# H3AR1.net
KiCad netlist of a schematic drawn in EAGLE
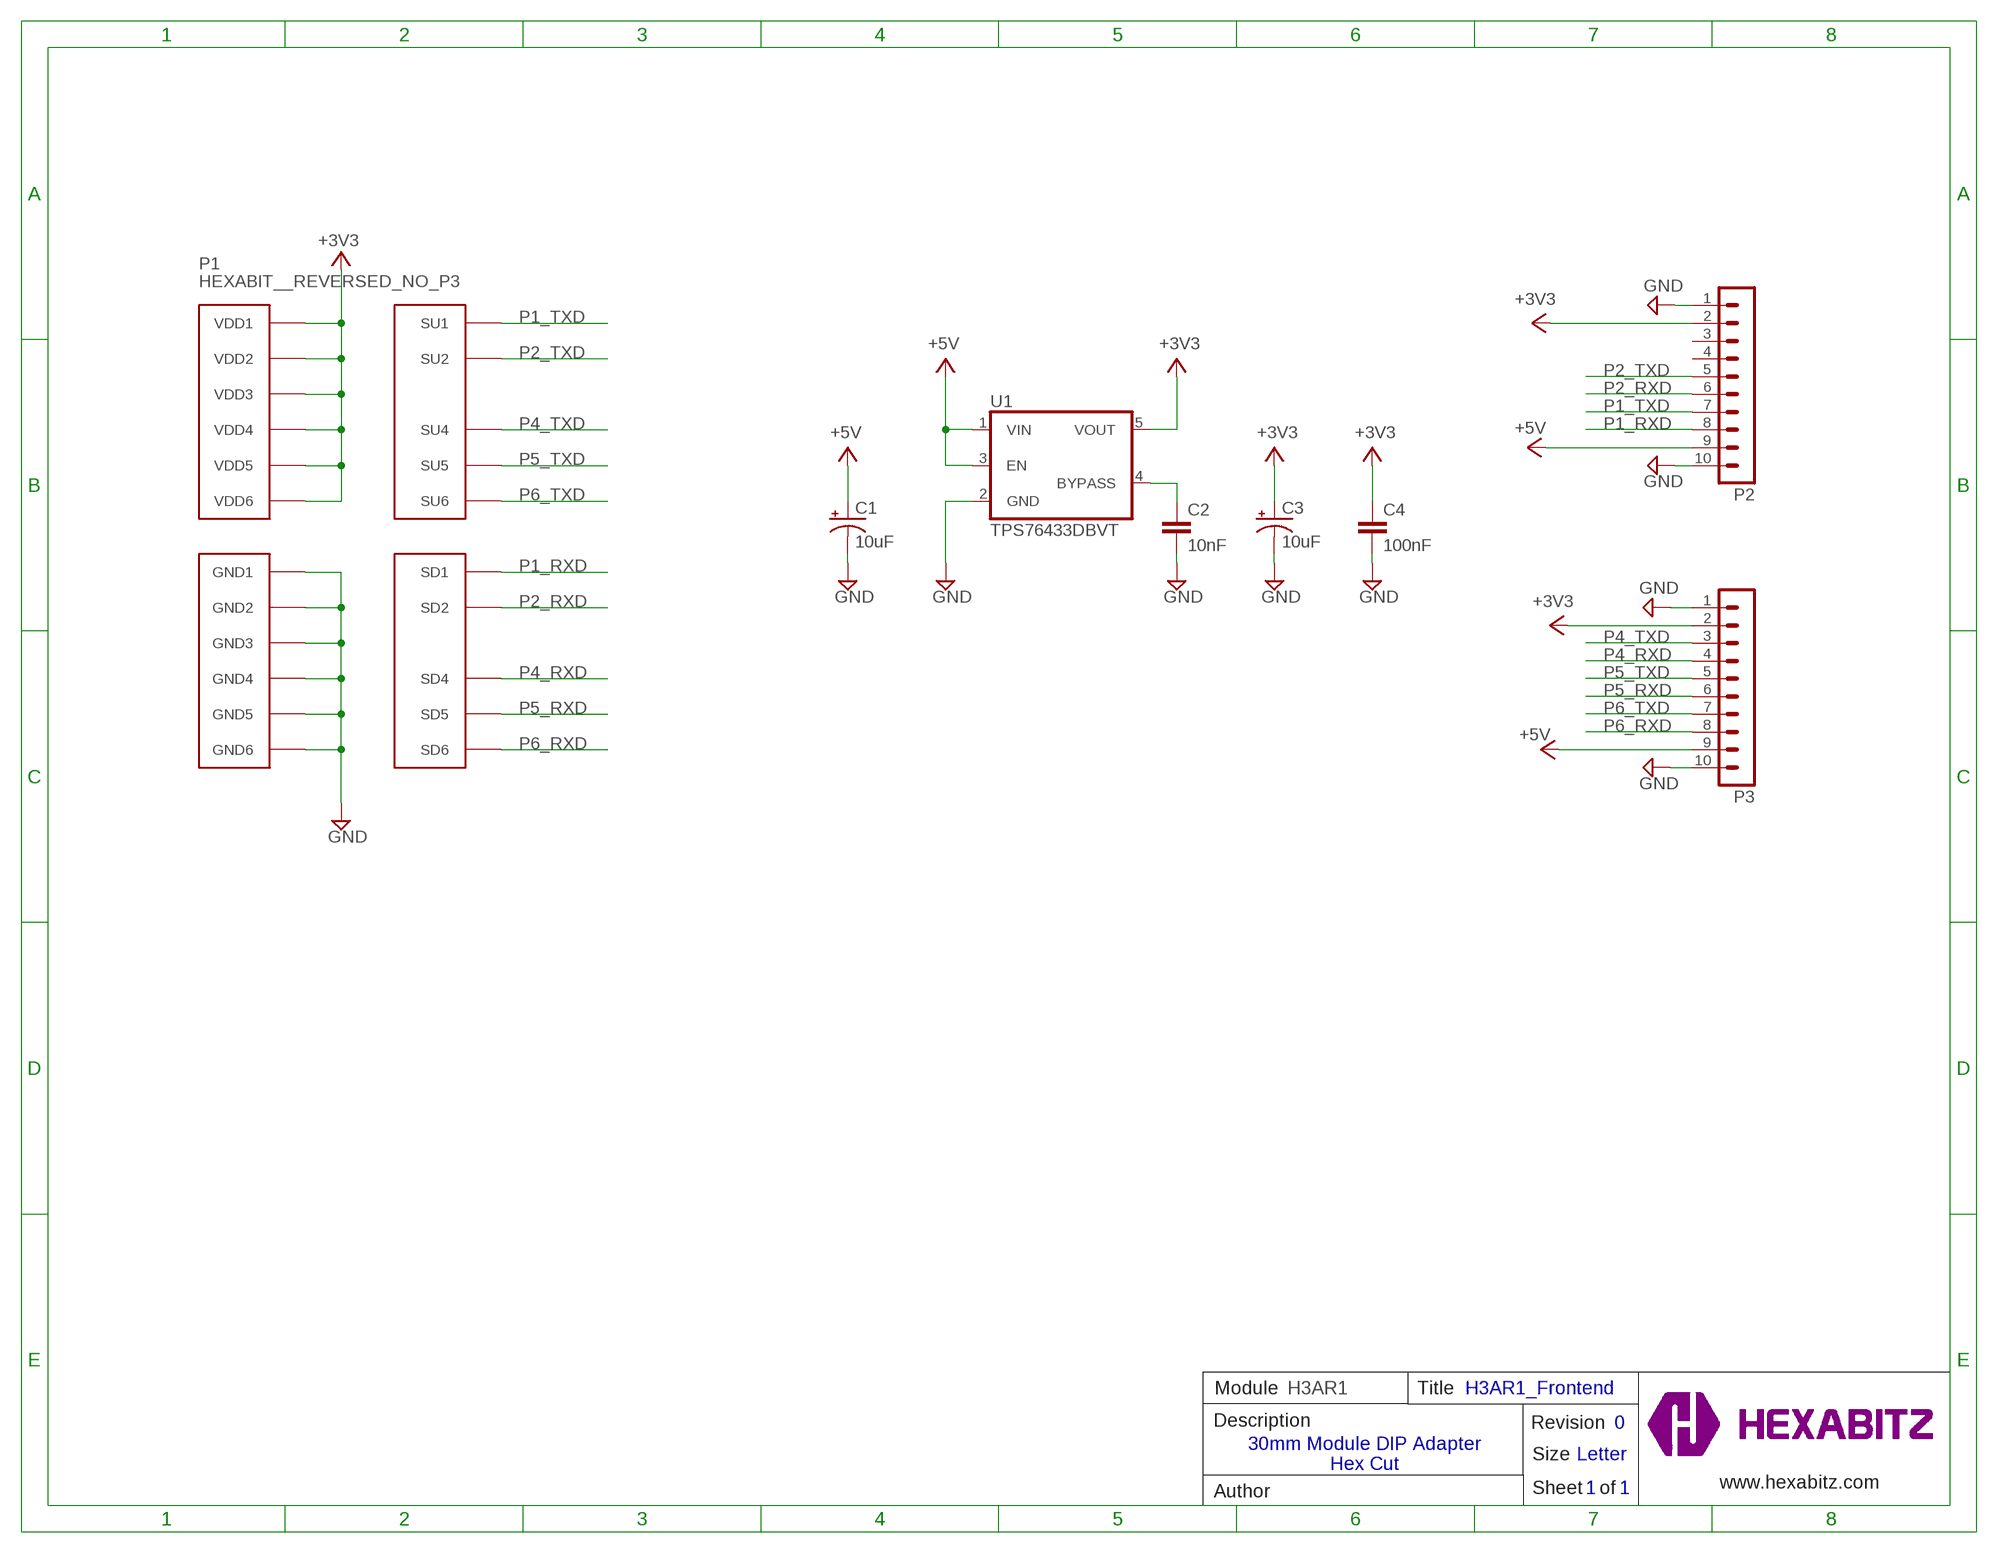
[diagram p0: schematic, sheet 1]

(export (version "E")
  (design (tool "Eeschema 10.0.6"))
  (components
    (comp (ref "C1")
      (value "10uF")
      (footprint "eagle-import:C-1210-POL")
      (fields
        (field (name "CAPACITANCE") "10uF")
        (field (name "MFN") "AVX")
        (field (name "MPN") "TPSB106K016R0500")
        (field (name "OCTOPART_URL") "https://octopart.com/tpsb106k016r0500-avx-1436890?r=sp#")
      )
      (libsource (lib "eagle-import") (part "C-1210-POL"))
    )
    (comp (ref "C2")
      (value "10nF")
      (footprint "eagle-import:C-0603")
      (fields
        (field (name "CAPACITANCE") "10nF")
        (field (name "MFN") "KEMET")
        (field (name "MPN") "C0603C103K5RACTU")
        (field (name "OCTOPART_URL") "https://octopart.com/c0603c103k5ractu-kemet-133094?r=sp&s=R_iPBxLnSmGqhkU2rIMFpg")
        (field (name "TOLERANCE") "10%")
        (field (name "VOLTAGE_RATING") "50V")
      )
      (libsource (lib "eagle-import") (part "C-0603"))
    )
    (comp (ref "C3")
      (value "10uF")
      (footprint "eagle-import:C-1210-POL")
      (fields
        (field (name "CAPACITANCE") "10uF")
        (field (name "MFN") "AVX")
        (field (name "MPN") "TPSB106K016R0500")
        (field (name "OCTOPART_URL") "https://octopart.com/tpsb106k016r0500-avx-1436890?r=sp#")
      )
      (libsource (lib "eagle-import") (part "C-1210-POL"))
    )
    (comp (ref "C4")
      (value "100nF")
      (footprint "eagle-import:C-0603")
      (fields
        (field (name "CAPACITANCE") "100nF")
        (field (name "MFN") "KEMET")
        (field (name "MPN") "C0603C104K8RACTU")
        (field (name "OCTOPART_URL") "https://octopart.com/c0603c104k8ractu-kemet-145075?r=sp&s=9bS9ASSwSEqMCE9KBEQZ0g")
        (field (name "TOLERANCE") "10%")
        (field (name "VOLTAGE_RATING") "10V")
      )
      (libsource (lib "eagle-import") (part "C-0603"))
    )
    (comp (ref "P1")
      (value "HEXABIT__REVERSED_NO_P3")
      (footprint "eagle-import:HEXABIT_17.60_REVERSED_NO_P3")
      (libsource (lib "eagle-import") (part "HEXABIT_?_REVERSED_NO_P3"))
    )
    (comp (ref "P2")
      (value "MA10-1")
      (footprint "eagle-import:MA10-1")
      (fields (field (name "MPN") "61301011121"))
      (libsource (lib "eagle-import") (part "MA10-1"))
    )
    (comp (ref "P3")
      (value "MA10-1")
      (footprint "eagle-import:MA10-1")
      (fields (field (name "MPN") "61301011121"))
      (libsource (lib "eagle-import") (part "MA10-1"))
    )
    (comp (ref "TRIMBLE-LOGO1")
      (value "HEXA-LOGO")
      (footprint "eagle-import:HEXA-LOGO")
      (libsource (lib "eagle-import") (part "HEXA-LOGO"))
    )
    (comp (ref "U1")
      (value "TPS76433DBVT")
      (footprint "eagle-import:SOT25")
      (libsource (lib "eagle-import") (part "TPS764DBVT33"))
    )
  )
  (nets
    (net (code "1") (name "+3V3") (class "Default")
      (node (ref "C3") (pin "1") (pinfunction "+_1") (pintype "passive"))
      (node (ref "C4") (pin "1") (pinfunction "1_1") (pintype "passive"))
      (node (ref "P1") (pin "PAD_PU10") (pinfunction "VDD4_PAD_PU10") (pintype "power_in"))
      (node (ref "P1") (pin "PAD_PU11") (pinfunction "VDD5_PAD_PU11") (pintype "power_in"))
      (node (ref "P1") (pin "PAD_PU12") (pinfunction "VDD6_PAD_PU12") (pintype "power_in"))
      (node (ref "P1") (pin "PAD_PU7") (pinfunction "VDD1_PAD_PU7") (pintype "power_in"))
      (node (ref "P1") (pin "PAD_PU8") (pinfunction "VDD2_PAD_PU8") (pintype "power_in"))
      (node (ref "P1") (pin "PAD_PU9") (pinfunction "VDD3_PAD_PU9") (pintype "power_in"))
      (node (ref "P2") (pin "2") (pinfunction "2_2") (pintype "passive"))
      (node (ref "P3") (pin "2") (pinfunction "2_2") (pintype "passive"))
      (node (ref "U1") (pin "5") (pinfunction "VOUT_5") (pintype "passive"))
    )
    (net (code "2") (name "+5V") (class "Default")
      (node (ref "C1") (pin "1") (pinfunction "+_1") (pintype "passive"))
      (node (ref "P2") (pin "9") (pinfunction "9_9") (pintype "passive"))
      (node (ref "P3") (pin "9") (pinfunction "9_9") (pintype "passive"))
      (node (ref "U1") (pin "1") (pinfunction "VIN_1") (pintype "input"))
      (node (ref "U1") (pin "3") (pinfunction "EN_3") (pintype "input"))
    )
    (net (code "3") (name "/P1_RXD") (class "Default")
      (node (ref "P1") (pin "PAD_PD1") (pinfunction "SD1_PAD_PD1") (pintype "bidirectional"))
      (node (ref "P2") (pin "8") (pinfunction "8_8") (pintype "passive"))
    )
    (net (code "4") (name "/P1_TXD") (class "Default")
      (node (ref "P1") (pin "PAD_PU1") (pinfunction "SU1_PAD_PU1") (pintype "bidirectional"))
      (node (ref "P2") (pin "7") (pinfunction "7_7") (pintype "passive"))
    )
    (net (code "5") (name "/P2_RXD") (class "Default")
      (node (ref "P1") (pin "PAD_PD2") (pinfunction "SD2_PAD_PD2") (pintype "bidirectional"))
      (node (ref "P2") (pin "6") (pinfunction "6_6") (pintype "passive"))
    )
    (net (code "6") (name "/P2_TXD") (class "Default")
      (node (ref "P1") (pin "PAD_PU2") (pinfunction "SU2_PAD_PU2") (pintype "bidirectional"))
      (node (ref "P2") (pin "5") (pinfunction "5_5") (pintype "passive"))
    )
    (net (code "7") (name "/P4_RXD") (class "Default")
      (node (ref "P1") (pin "PAD_PD4") (pinfunction "SD4_PAD_PD4") (pintype "bidirectional"))
      (node (ref "P3") (pin "4") (pinfunction "4_4") (pintype "passive"))
    )
    (net (code "8") (name "/P4_TXD") (class "Default")
      (node (ref "P1") (pin "PAD_PU4") (pinfunction "SU4_PAD_PU4") (pintype "bidirectional"))
      (node (ref "P3") (pin "3") (pinfunction "3_3") (pintype "passive"))
    )
    (net (code "9") (name "/P5_RXD") (class "Default")
      (node (ref "P1") (pin "PAD_PD5") (pinfunction "SD5_PAD_PD5") (pintype "bidirectional"))
      (node (ref "P3") (pin "6") (pinfunction "6_6") (pintype "passive"))
    )
    (net (code "10") (name "/P5_TXD") (class "Default")
      (node (ref "P1") (pin "PAD_PU5") (pinfunction "SU5_PAD_PU5") (pintype "bidirectional"))
      (node (ref "P3") (pin "5") (pinfunction "5_5") (pintype "passive"))
    )
    (net (code "11") (name "/P6_RXD") (class "Default")
      (node (ref "P1") (pin "PAD_PD6") (pinfunction "SD6_PAD_PD6") (pintype "bidirectional"))
      (node (ref "P3") (pin "8") (pinfunction "8_8") (pintype "passive"))
    )
    (net (code "12") (name "/P6_TXD") (class "Default")
      (node (ref "P1") (pin "PAD_PU6") (pinfunction "SU6_PAD_PU6") (pintype "bidirectional"))
      (node (ref "P3") (pin "7") (pinfunction "7_7") (pintype "passive"))
    )
    (net (code "13") (name "GND") (class "Default")
      (node (ref "C1") (pin "2") (pinfunction "-_2") (pintype "passive"))
      (node (ref "C2") (pin "2") (pinfunction "2_2") (pintype "passive"))
      (node (ref "C3") (pin "2") (pinfunction "-_2") (pintype "passive"))
      (node (ref "C4") (pin "2") (pinfunction "2_2") (pintype "passive"))
      (node (ref "P1") (pin "PAD_PD10") (pinfunction "GND4_PAD_PD10") (pintype "power_in"))
      (node (ref "P1") (pin "PAD_PD11") (pinfunction "GND5_PAD_PD11") (pintype "power_in"))
      (node (ref "P1") (pin "PAD_PD12") (pinfunction "GND6_PAD_PD12") (pintype "power_in"))
      (node (ref "P1") (pin "PAD_PD7") (pinfunction "GND1_PAD_PD7") (pintype "power_in"))
      (node (ref "P1") (pin "PAD_PD8") (pinfunction "GND2_PAD_PD8") (pintype "power_in"))
      (node (ref "P1") (pin "PAD_PD9") (pinfunction "GND3_PAD_PD9") (pintype "power_in"))
      (node (ref "P2") (pin "1") (pinfunction "1_1") (pintype "passive"))
      (node (ref "P2") (pin "10") (pinfunction "10_10") (pintype "passive"))
      (node (ref "P3") (pin "1") (pinfunction "1_1") (pintype "passive"))
      (node (ref "P3") (pin "10") (pinfunction "10_10") (pintype "passive"))
      (node (ref "U1") (pin "2") (pinfunction "GND_2") (pintype "passive"))
    )
    (net (code "14") (name "Net-(U1-BYPASS)") (class "Default")
      (node (ref "C2") (pin "1") (pinfunction "1_1") (pintype "passive"))
      (node (ref "U1") (pin "4") (pinfunction "BYPASS_4") (pintype "input"))
    )
    (net (code "15") (name "unconnected-(P2-Pad3)") (class "Default")
      (node (ref "P2") (pin "3") (pinfunction "3_3") (pintype "passive"))
    )
    (net (code "16") (name "unconnected-(P2-Pad4)") (class "Default")
      (node (ref "P2") (pin "4") (pinfunction "4_4") (pintype "passive"))
    )
  )
)
